# OpenTCU.net
KiCad netlist of a schematic drawn in EasyEDA
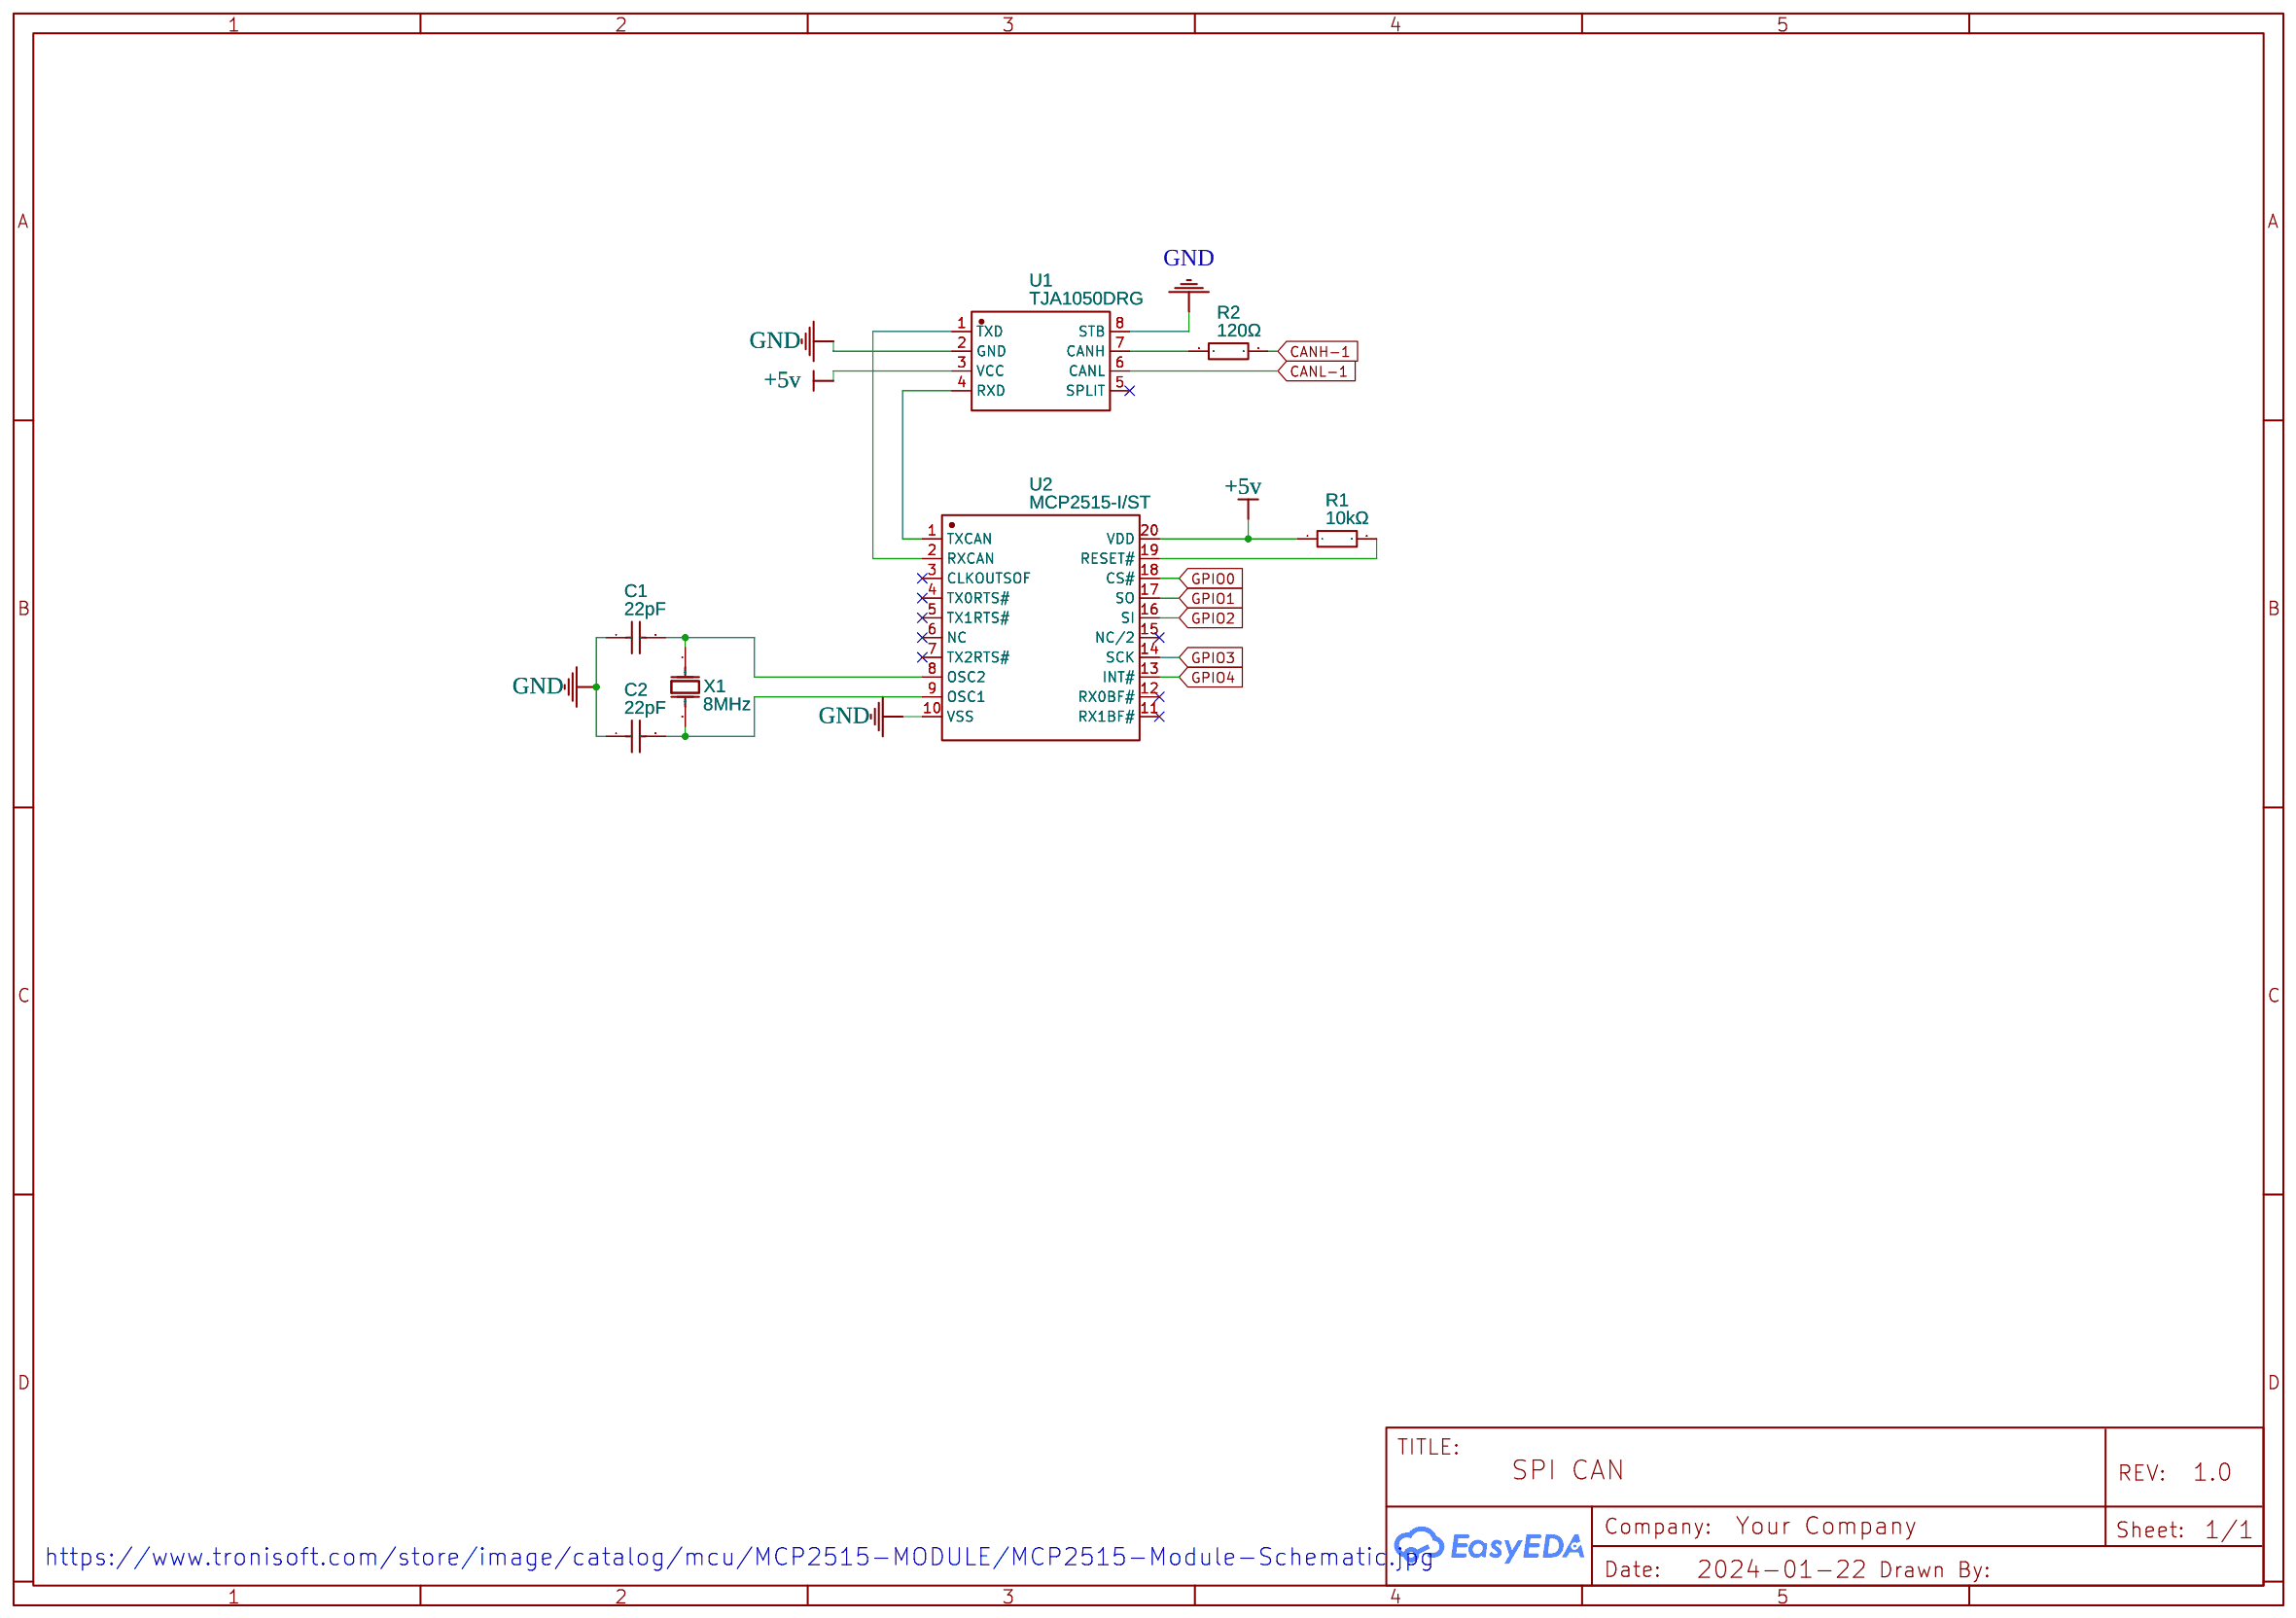
[diagram p0: SPI CAN]
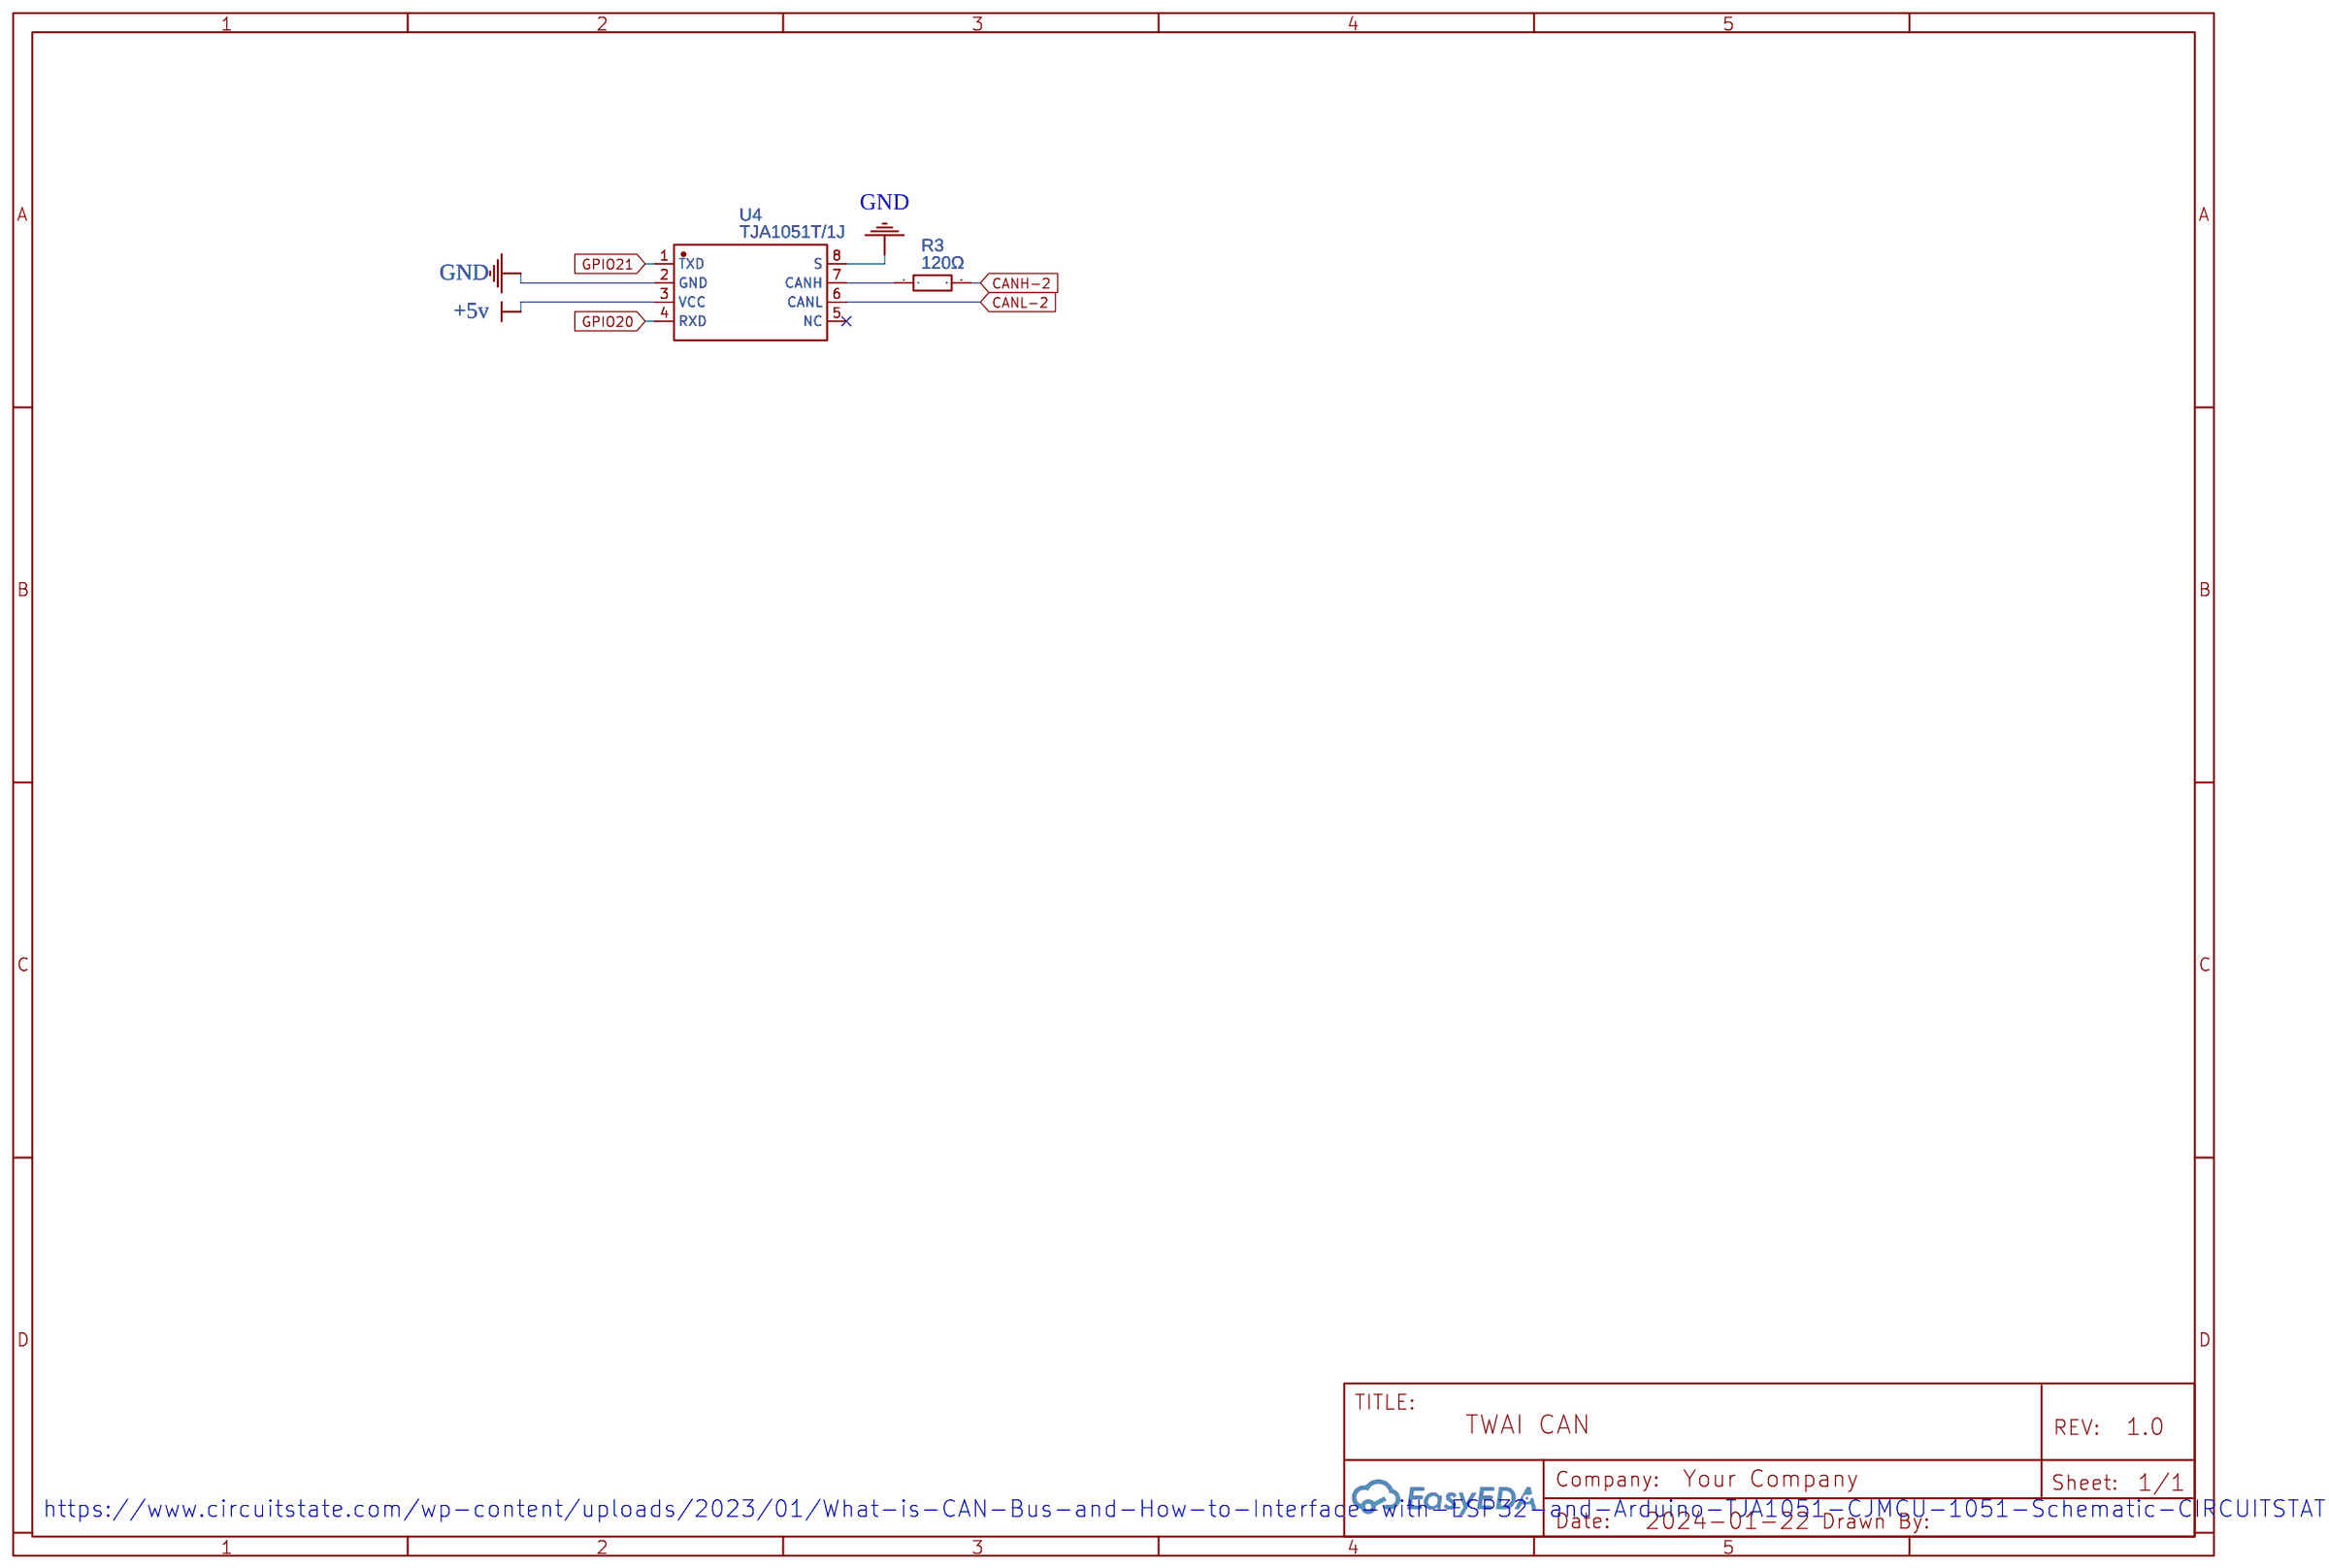
[diagram p1: TWAI CAN]
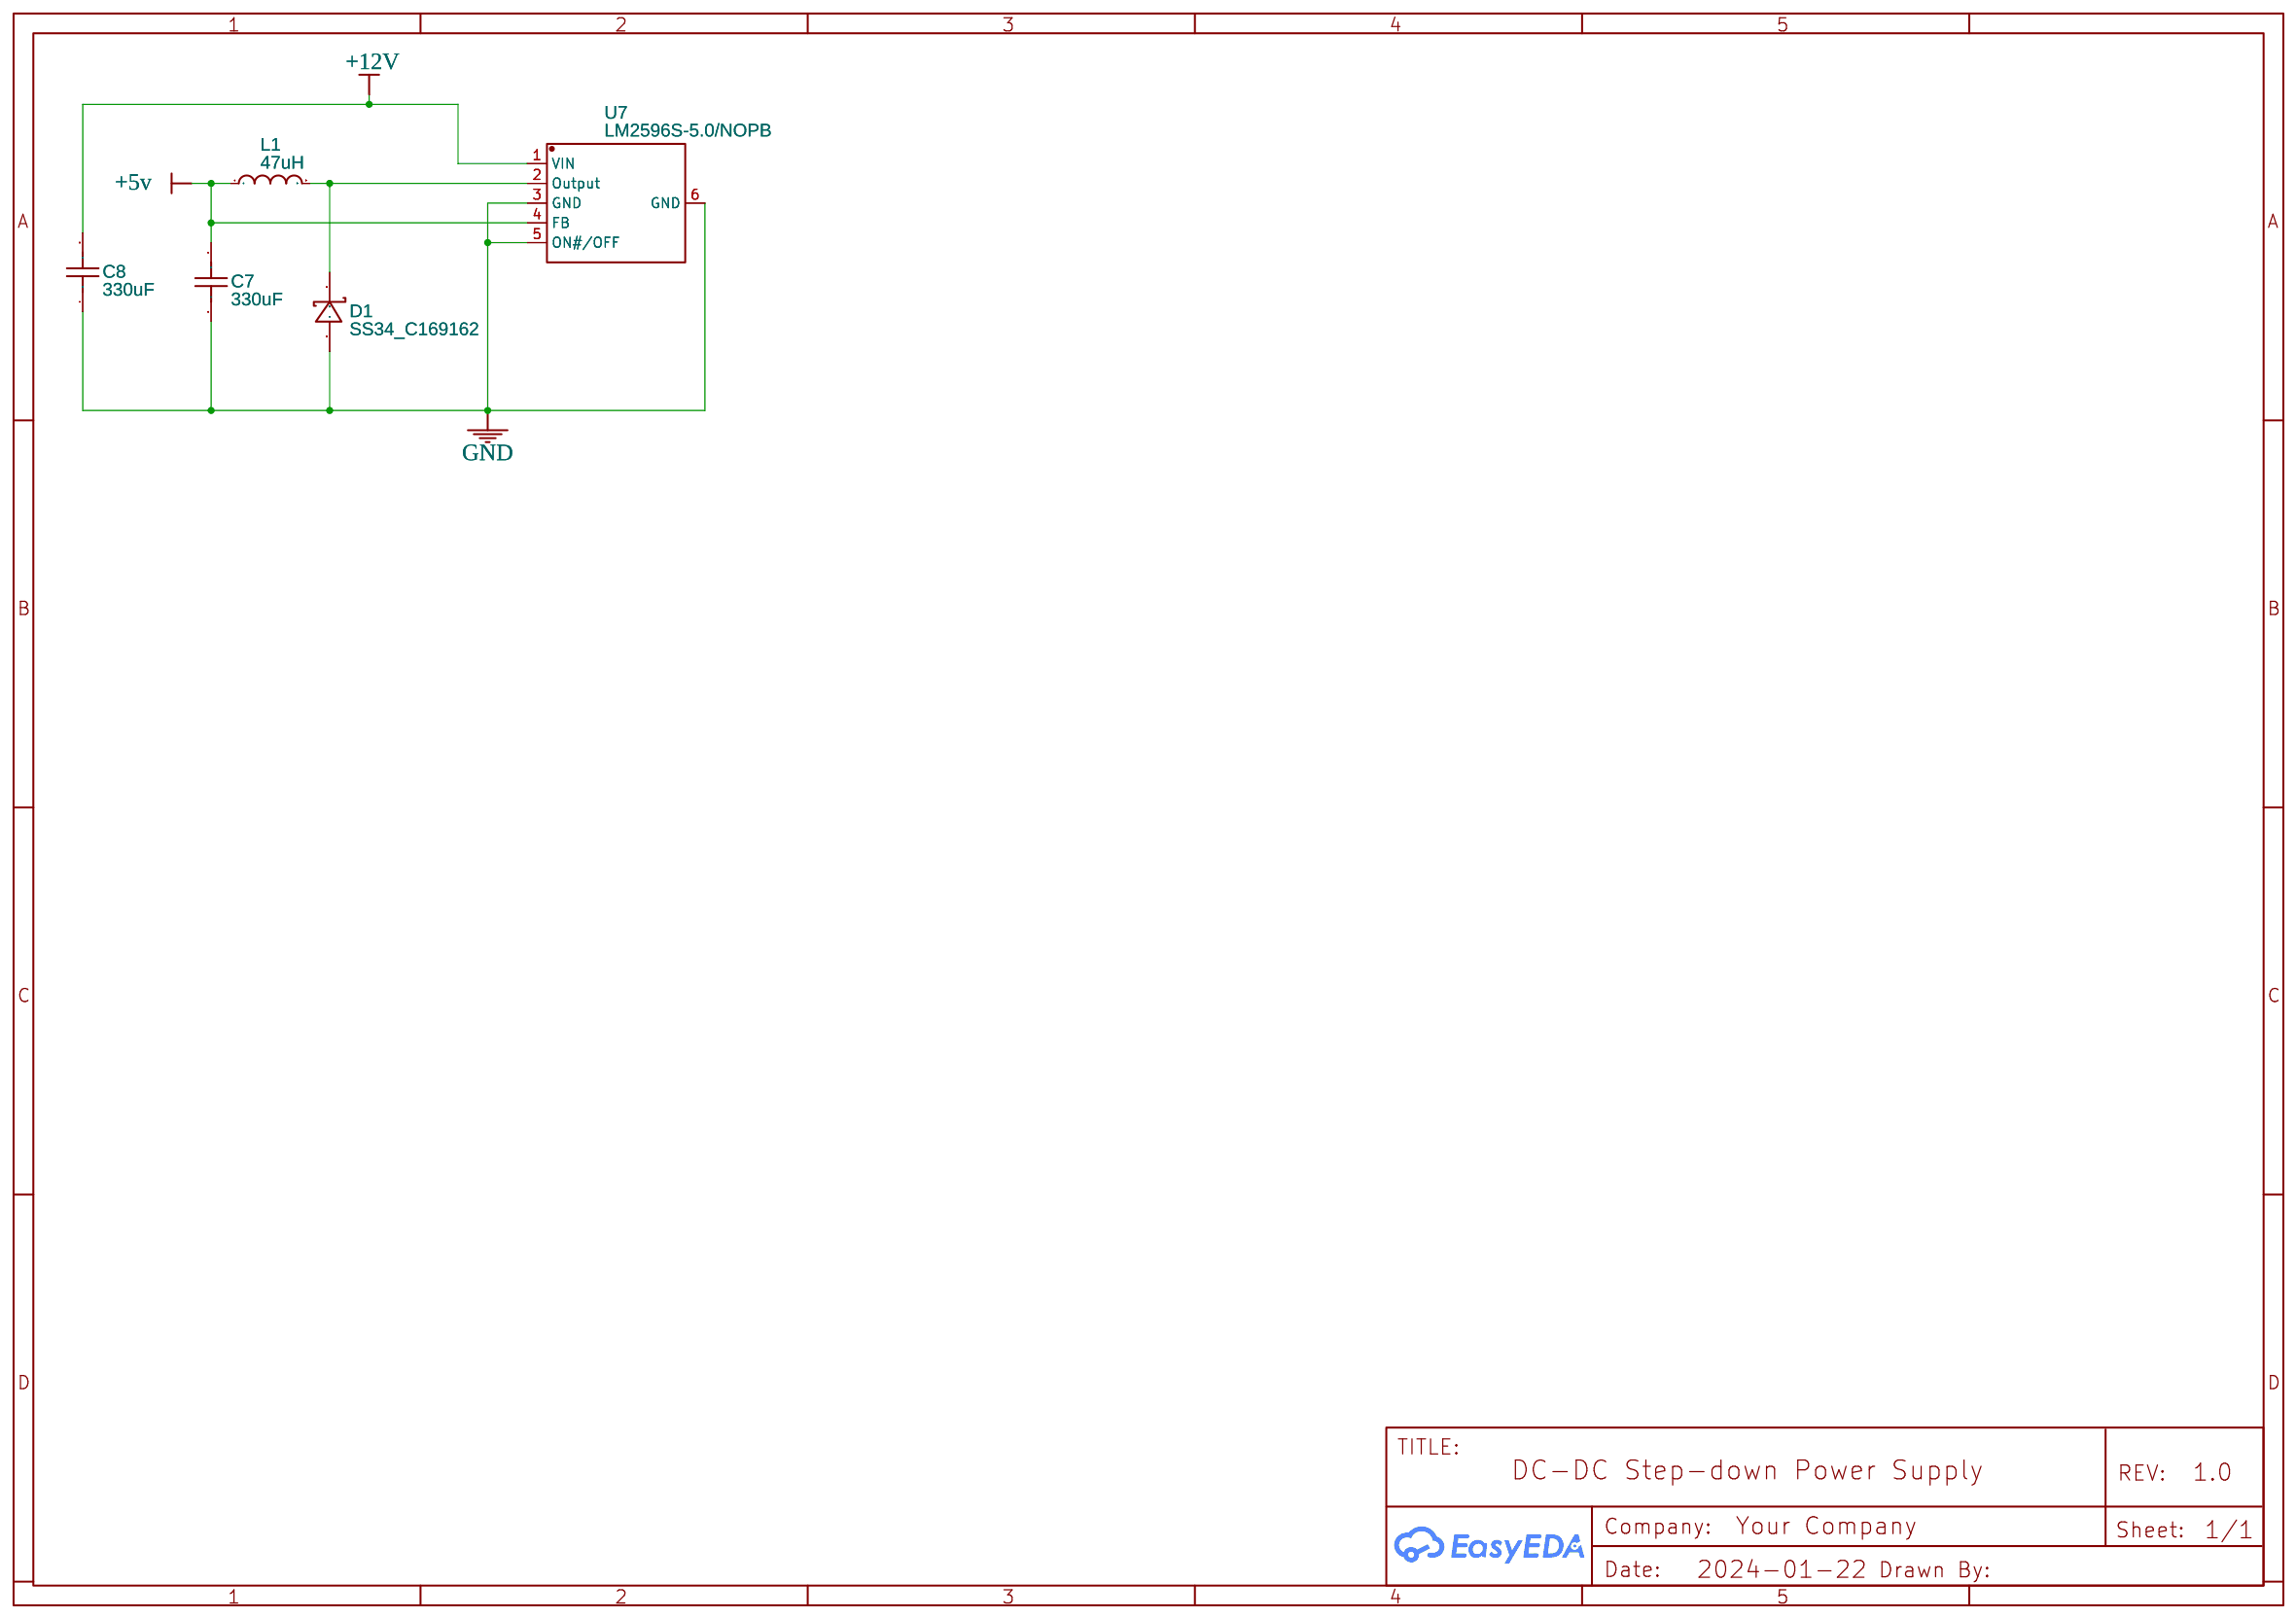
[diagram p2: DC-DC Step-down Power Supply]
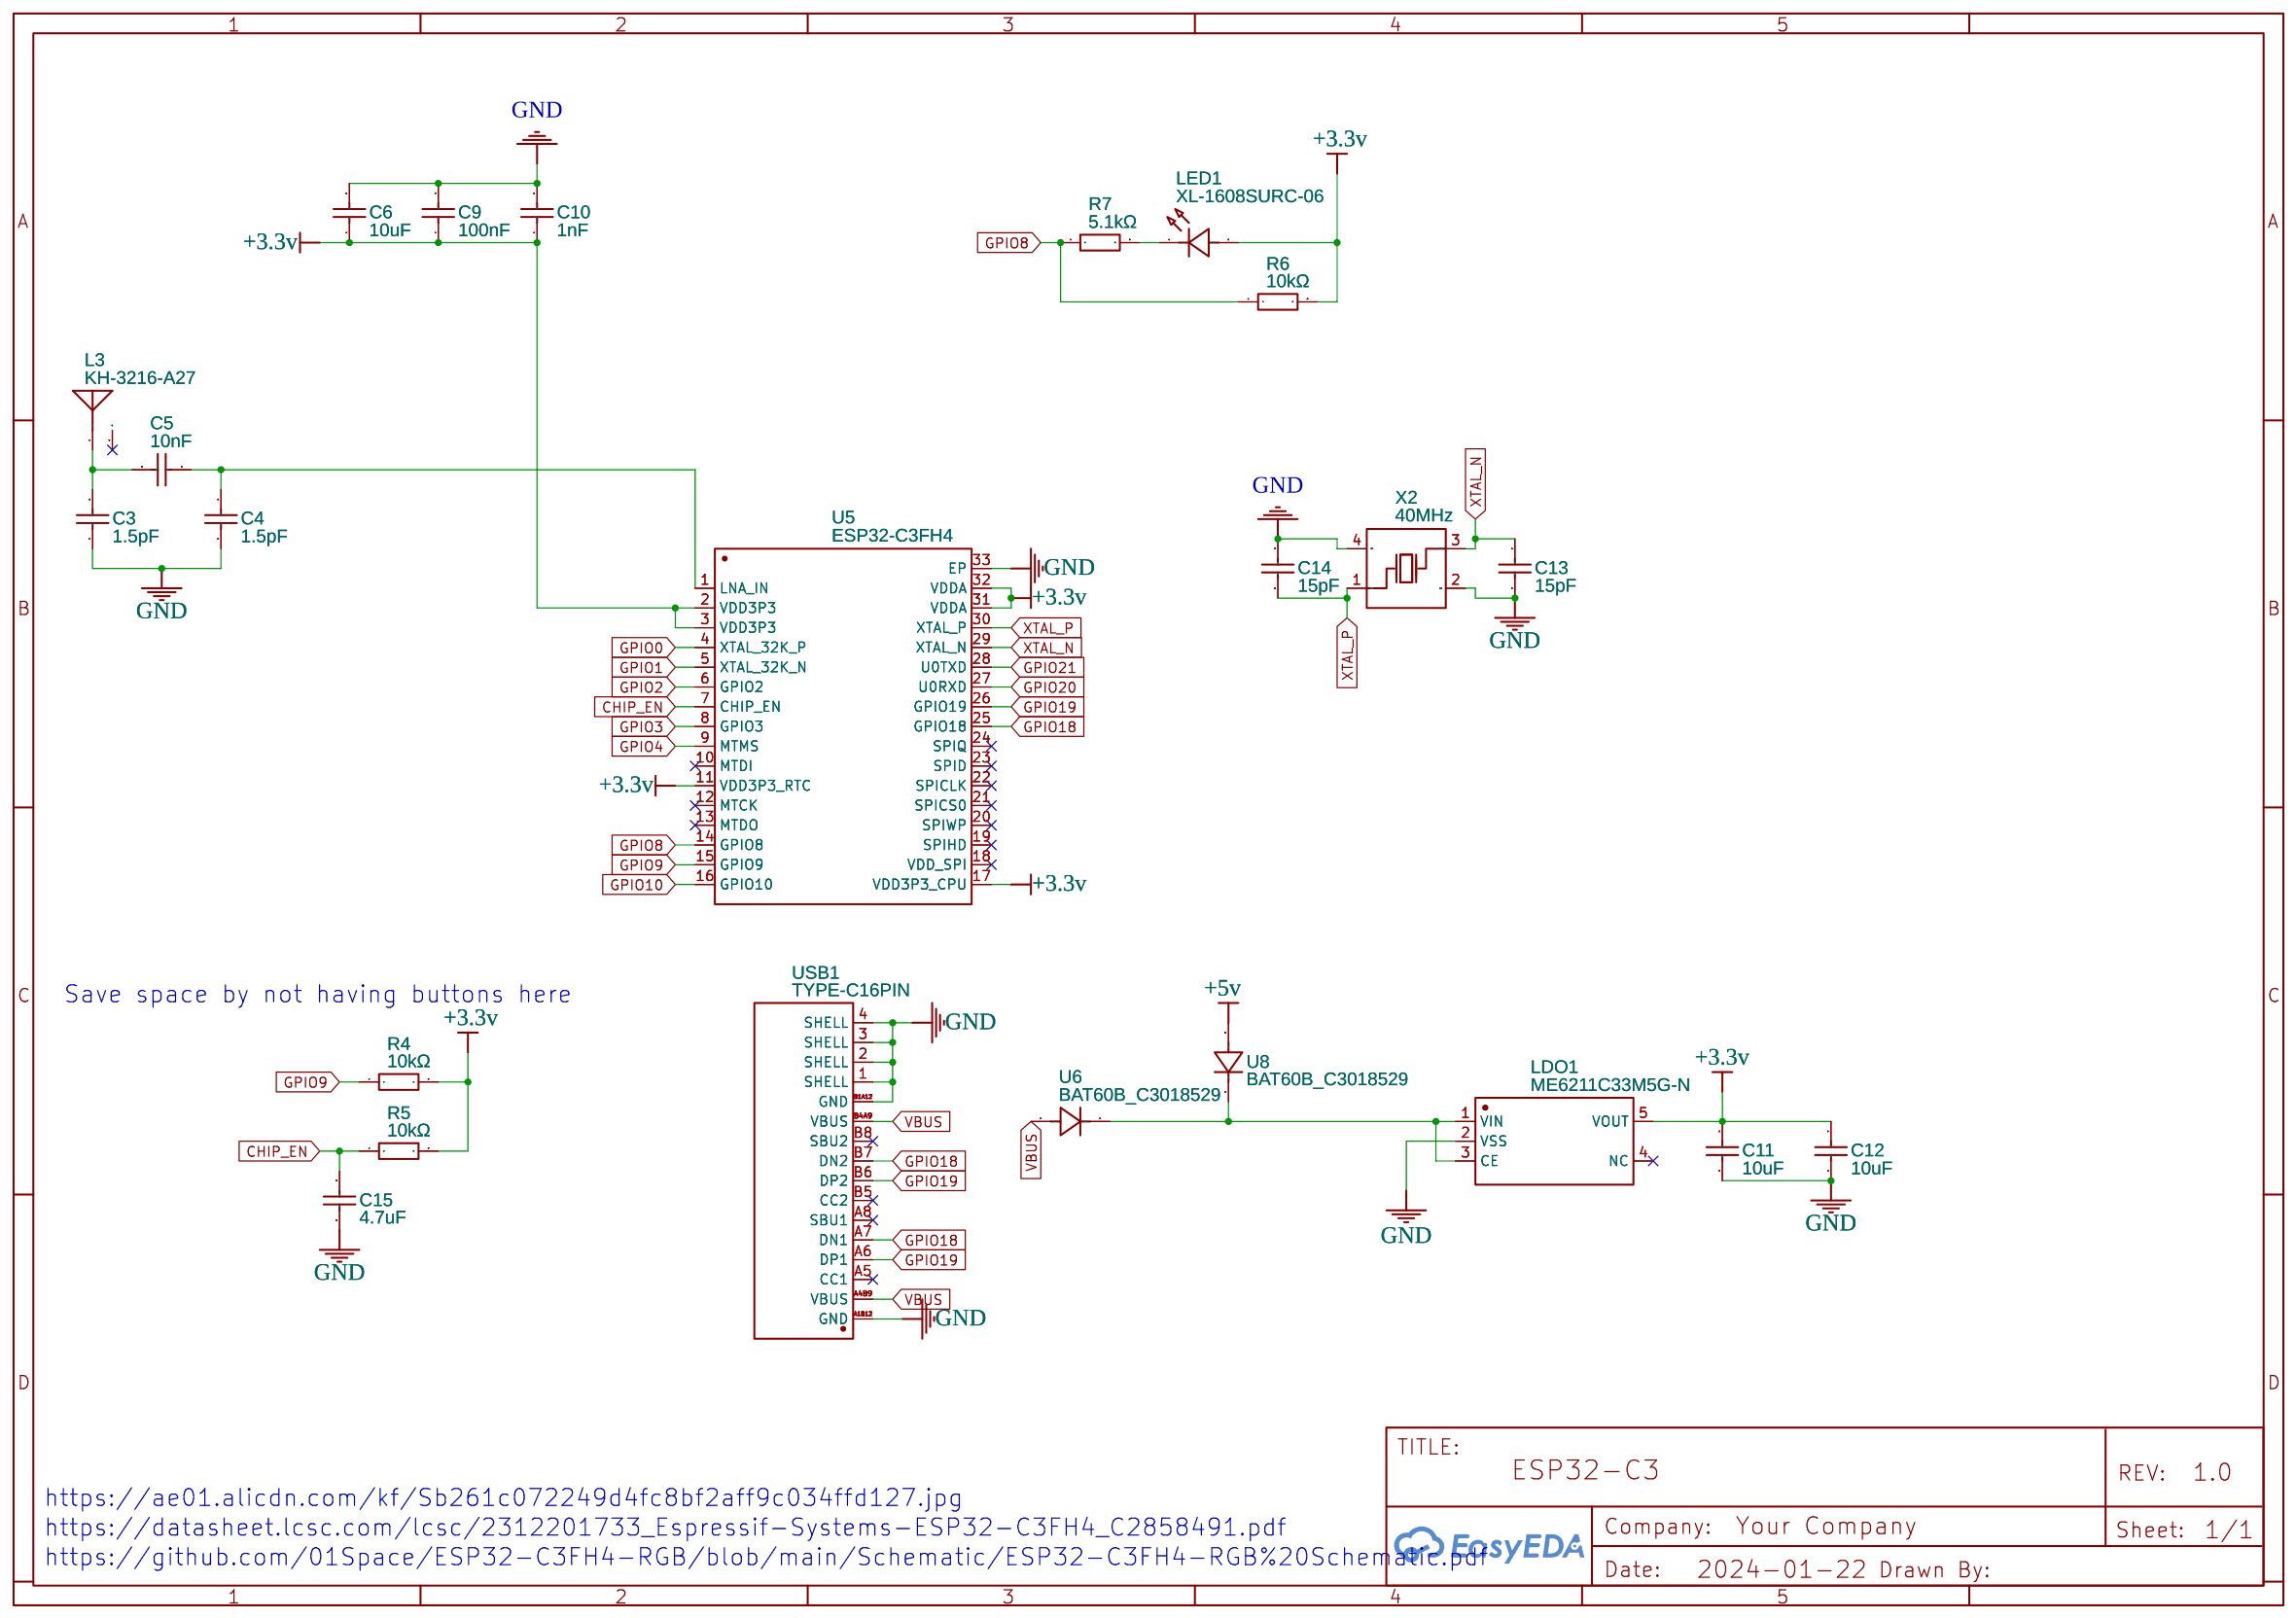
[diagram p3: ESP32-C3]
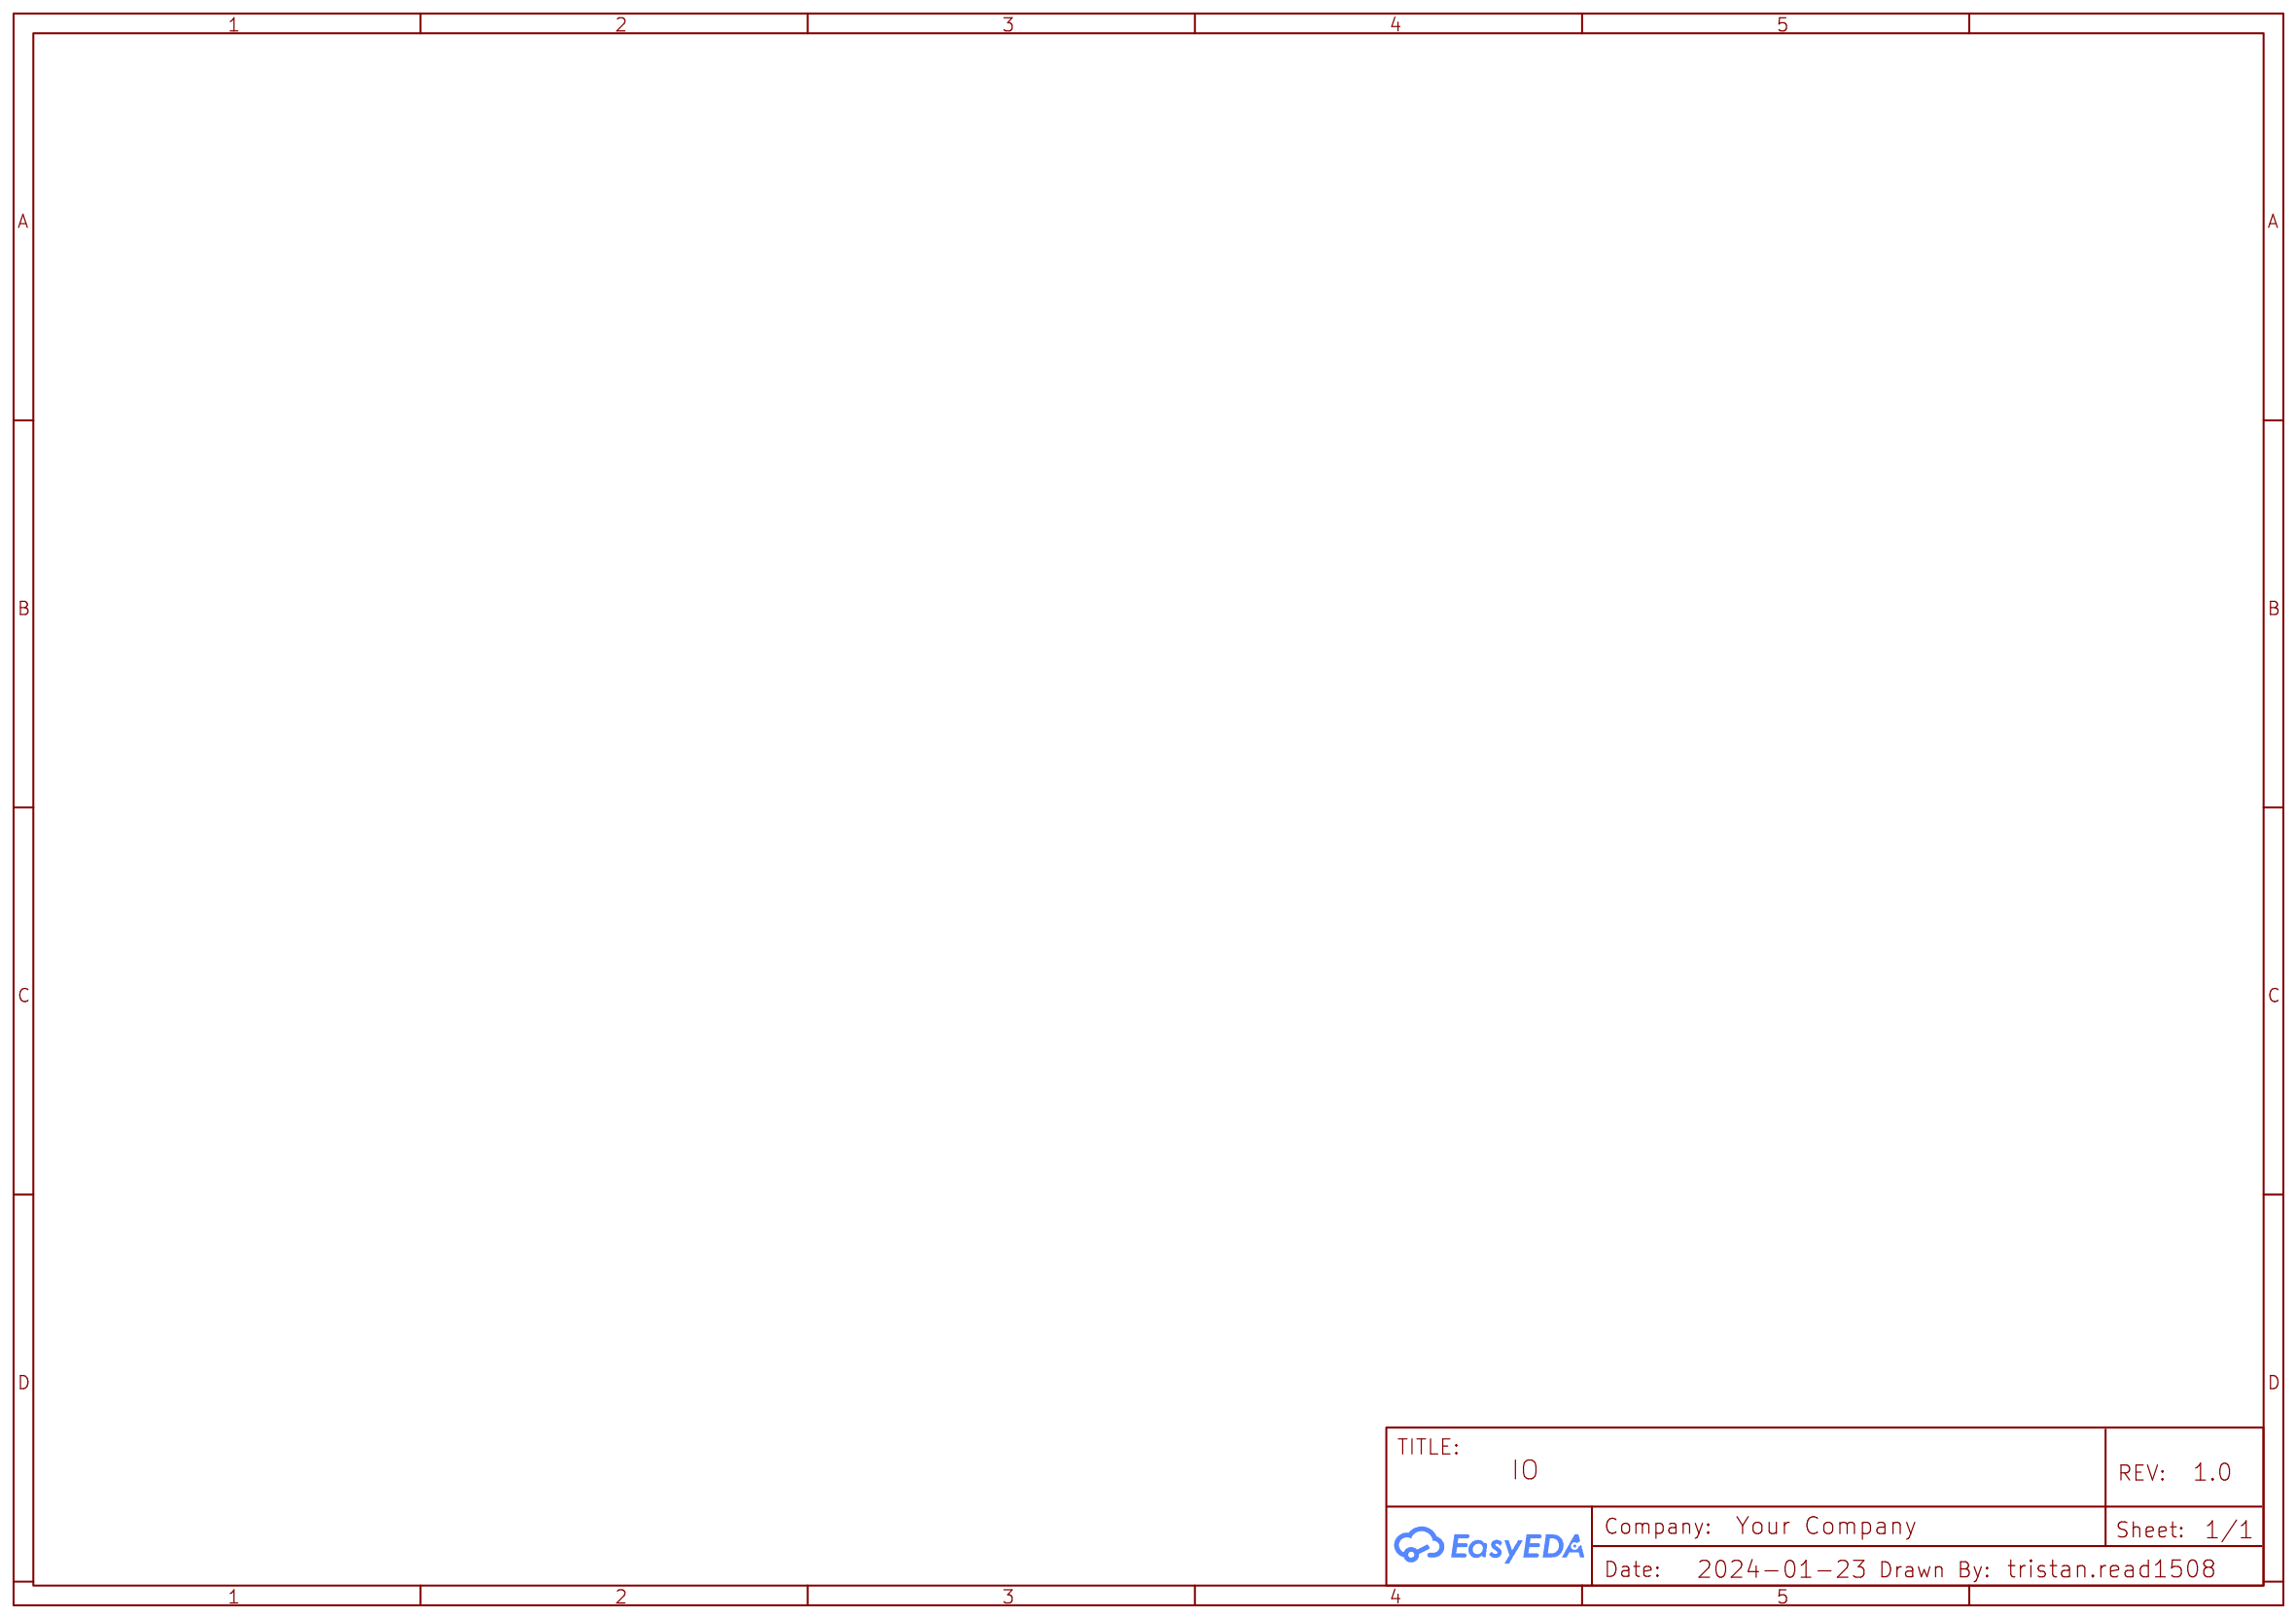
[diagram p4: IO]

(export (version "E")
  (design (tool "Eeschema 10.0.6"))
  (components
    (comp (ref "C1")
      (value "22pF")
      (fields (field (name "Manufacturer Part") "0402CG220J500NT") (field (name "Manufacturer") "FH(风华)"))
      (libsource (lib "") (part "0402CG220J500NT"))
    )
    (comp (ref "C2")
      (value "22pF")
      (fields (field (name "Manufacturer Part") "0402CG220J500NT") (field (name "Manufacturer") "FH(风华)"))
      (libsource (lib "") (part "0402CG220J500NT"))
    )
    (comp (ref "R1")
      (value "10kΩ")
      (fields (field (name "Manufacturer Part") "RC0603FR-0710KL") (field (name "Manufacturer") "YAGEO(国巨)"))
      (libsource (lib "") (part "RC0603FR-0710KL"))
    )
    (comp (ref "R2")
      (value "120Ω")
      (fields
        (field (name "Manufacturer Part") "0603WAF1200T5E")
        (field (name "Manufacturer") "UNI-ROYAL(厚声)")
      )
      (libsource (lib "") (part "0603WAF1200T5E"))
    )
    (comp (ref "U1")
      (value "TJA1050DRG")
      (fields (field (name "Manufacturer") "HGC(深圳汉芯)"))
      (libsource (lib "") (part "TJA1050DRG"))
    )
    (comp (ref "U2")
      (value "MCP2515-I/ST")
      (fields (field (name "Manufacturer") "MICROCHIP(美国微芯)"))
      (libsource (lib "") (part "MCP2515-I/ST"))
    )
    (comp (ref "X1")
      (value "8MHz")
      (fields (field (name "Manufacturer Part") "X50328MSB2GI") (field (name "Manufacturer") "YXC(扬兴晶振)"))
      (libsource (lib "") (part "X50328MSB2GI"))
    )
    (comp (ref "R3")
      (value "120Ω")
      (fields
        (field (name "Manufacturer Part") "0603WAF1200T5E")
        (field (name "Manufacturer") "UNI-ROYAL(厚声)")
      )
      (libsource (lib "") (part "0603WAF1200T5E"))
    )
    (comp (ref "U4")
      (value "TJA1051T/1J")
      (fields (field (name "Manufacturer") "NXP(恩智浦)"))
      (libsource (lib "") (part "TJA1051T/1J"))
    )
    (comp (ref "C7")
      (value "330uF")
      (fields
        (field (name "Manufacturer Part") "GRM32ER60G337ME05L")
        (field (name "Manufacturer") "muRata(村田)")
      )
      (libsource (lib "") (part "GRM32ER60G337ME05L_1"))
    )
    (comp (ref "C8")
      (value "330uF")
      (fields
        (field (name "Manufacturer Part") "GRM32ER60G337ME05L")
        (field (name "Manufacturer") "muRata(村田)")
      )
      (libsource (lib "") (part "GRM32ER60G337ME05L"))
    )
    (comp (ref "D1")
      (value "SS34_C169162")
      (fields (field (name "Manufacturer Part") "SS34"))
      (libsource (lib "") (part "SS34_C169162"))
    )
    (comp (ref "L1")
      (value "47uH")
      (fields (field (name "Manufacturer Part") "CYA0650-47UH") (field (name "Manufacturer") "SHOU HAN(首韩)"))
      (libsource (lib "") (part "CYA0650-47UH"))
    )
    (comp (ref "U7")
      (value "LM2596S-5.0/NOPB")
      (fields (field (name "Manufacturer") "TI(德州仪器)"))
      (libsource (lib "") (part "LM2596S-5.0/NOPB"))
    )
    (comp (ref "C3")
      (value "1.5pF")
      (fields (field (name "Manufacturer Part") "0402CG1R5C500NT") (field (name "Manufacturer") "FH(风华)"))
      (libsource (lib "") (part "0402CG1R5C500NT"))
    )
    (comp (ref "C4")
      (value "1.5pF")
      (fields (field (name "Manufacturer Part") "0402CG1R5C500NT") (field (name "Manufacturer") "FH(风华)"))
      (libsource (lib "") (part "0402CG1R5C500NT"))
    )
    (comp (ref "C5")
      (value "10nF")
      (fields
        (field (name "Manufacturer Part") "CC0402KRX7R9BB103")
        (field (name "Manufacturer") "YAGEO(国巨)")
      )
      (libsource (lib "") (part "CC0402KRX7R9BB103"))
    )
    (comp (ref "C6")
      (value "10uF")
      (fields
        (field (name "Manufacturer Part") "CL05A106MQ5NUNC")
        (field (name "Manufacturer") "SAMSUNG(三星)")
      )
      (libsource (lib "") (part "CL05A106MQ5NUNC"))
    )
    (comp (ref "C9")
      (value "100nF")
      (fields (field (name "Manufacturer Part") "0603B104K500NT") (field (name "Manufacturer") "FH(风华)"))
      (libsource (lib "") (part "0603B104K500NT"))
    )
    (comp (ref "C10")
      (value "1nF")
      (fields
        (field (name "Manufacturer Part") "CC0402KRX7R9BB102")
        (field (name "Manufacturer") "YAGEO(国巨)")
      )
      (libsource (lib "") (part "CC0402KRX7R9BB102"))
    )
    (comp (ref "C11")
      (value "10uF")
      (fields
        (field (name "Manufacturer Part") "CL05A106MQ5NUNC")
        (field (name "Manufacturer") "SAMSUNG(三星)")
      )
      (libsource (lib "") (part "CL05A106MQ5NUNC"))
    )
    (comp (ref "C12")
      (value "10uF")
      (fields
        (field (name "Manufacturer Part") "CL05A106MQ5NUNC")
        (field (name "Manufacturer") "SAMSUNG(三星)")
      )
      (libsource (lib "") (part "CL05A106MQ5NUNC"))
    )
    (comp (ref "C13")
      (value "15pF")
      (fields (field (name "Manufacturer Part") "0402CG150J500NT") (field (name "Manufacturer") "FH(风华)"))
      (libsource (lib "") (part "0402CG150J500NT"))
    )
    (comp (ref "C14")
      (value "15pF")
      (fields (field (name "Manufacturer Part") "0402CG150J500NT") (field (name "Manufacturer") "FH(风华)"))
      (libsource (lib "") (part "0402CG150J500NT"))
    )
    (comp (ref "C15")
      (value "4.7uF")
      (fields
        (field (name "Manufacturer Part") "CL10A475KP8NNNC")
        (field (name "Manufacturer") "SAMSUNG(三星)")
      )
      (libsource (lib "") (part "CL10A475KP8NNNC"))
    )
    (comp (ref "L3")
      (value "KH-3216-A27")
      (fields (field (name "Manufacturer") "kinghelm(金航标)"))
      (libsource (lib "") (part "KH-3216-A27"))
    )
    (comp (ref "LDO1")
      (value "ME6211C33M5G-N")
      (fields (field (name "Manufacturer") "MICRONE(南京微盟)"))
      (libsource (lib "") (part "ME6211C33M5G-N"))
    )
    (comp (ref "LED1")
      (value "XL-1608SURC-06")
      (fields (field (name "Manufacturer") "XINGLIGHT(成兴光)"))
      (libsource (lib "") (part "XL-1608SURC-06"))
    )
    (comp (ref "R4")
      (value "10kΩ")
      (fields (field (name "Manufacturer Part") "RC0603FR-0710KL") (field (name "Manufacturer") "YAGEO(国巨)"))
      (libsource (lib "") (part "RC0603FR-0710KL"))
    )
    (comp (ref "R5")
      (value "10kΩ")
      (fields (field (name "Manufacturer Part") "RC0603FR-0710KL") (field (name "Manufacturer") "YAGEO(国巨)"))
      (libsource (lib "") (part "RC0603FR-0710KL"))
    )
    (comp (ref "R6")
      (value "10kΩ")
      (fields (field (name "Manufacturer Part") "RC0603FR-0710KL") (field (name "Manufacturer") "YAGEO(国巨)"))
      (libsource (lib "") (part "RC0603FR-0710KL"))
    )
    (comp (ref "R7")
      (value "5.1kΩ")
      (fields
        (field (name "Manufacturer Part") "0603WAF5101T5E")
        (field (name "Manufacturer") "UNI-ROYAL(厚声)")
      )
      (libsource (lib "") (part "0603WAF5101T5E"))
    )
    (comp (ref "U5")
      (value "ESP32-C3FH4")
      (fields (field (name "Manufacturer") "ESPRESSIF(乐鑫)"))
      (libsource (lib "") (part "ESP32-C3FH4"))
    )
    (comp (ref "U6")
      (value "BAT60B_C3018529")
      (fields (field (name "Manufacturer Part") "BAT60B") (field (name "Manufacturer") "FUXINSEMI(富芯森美)"))
      (libsource (lib "") (part "BAT60B_C3018529_1"))
    )
    (comp (ref "U8")
      (value "BAT60B_C3018529")
      (fields (field (name "Manufacturer Part") "BAT60B") (field (name "Manufacturer") "FUXINSEMI(富芯森美)"))
      (libsource (lib "") (part "BAT60B_C3018529"))
    )
    (comp (ref "USB1")
      (value "TYPE-C16PIN")
      (fields (field (name "Manufacturer") "SHOU HAN(首韩)"))
      (libsource (lib "") (part "TYPE-C16PIN"))
    )
    (comp (ref "X2")
      (value "40MHz")
      (fields (field (name "Manufacturer Part") "X322540MPB4SI") (field (name "Manufacturer") "YXC(扬兴晶振)"))
      (libsource (lib "") (part "X322540MPB4SI"))
    )
  )
  (nets
    (net (code "1") (name "+3.3v") (class "Default")
      (node (ref "C10") (pin "1") (pinfunction "1_1") (pintype "input"))
      (node (ref "C11") (pin "2") (pinfunction "2_2") (pintype "input"))
      (node (ref "C12") (pin "2") (pinfunction "2_2") (pintype "input"))
      (node (ref "C6") (pin "1") (pinfunction "1_1") (pintype "input"))
      (node (ref "C9") (pin "1") (pinfunction "1_1") (pintype "input"))
      (node (ref "LDO1") (pin "5") (pinfunction "VOUT_5") (pintype "unspecified"))
      (node (ref "LED1") (pin "2") (pinfunction "A_2") (pintype "unspecified"))
      (node (ref "R4") (pin "2") (pinfunction "2_2") (pintype "input"))
      (node (ref "R5") (pin "2") (pinfunction "2_2") (pintype "input"))
      (node (ref "R6") (pin "2") (pinfunction "2_2") (pintype "input"))
      (node (ref "U5") (pin "11") (pinfunction "VDD3P3_RTC_11") (pintype "unspecified"))
      (node (ref "U5") (pin "17") (pinfunction "VDD3P3_CPU_17") (pintype "unspecified"))
      (node (ref "U5") (pin "2") (pinfunction "VDD3P3_2") (pintype "unspecified"))
      (node (ref "U5") (pin "3") (pinfunction "VDD3P3_3") (pintype "unspecified"))
      (node (ref "U5") (pin "31") (pinfunction "VDDA_31") (pintype "unspecified"))
      (node (ref "U5") (pin "32") (pinfunction "VDDA_32") (pintype "unspecified"))
    )
    (net (code "2") (name "+5v") (class "Default")
      (node (ref "C7") (pin "1") (pinfunction "1_1") (pintype "unspecified"))
      (node (ref "L1") (pin "1") (pinfunction "1_1") (pintype "unspecified"))
      (node (ref "R1") (pin "1") (pinfunction "1_1") (pintype "input"))
      (node (ref "U1") (pin "3") (pinfunction "VCC_3") (pintype "unspecified"))
      (node (ref "U2") (pin "20") (pinfunction "VDD_20") (pintype "unspecified"))
      (node (ref "U4") (pin "3") (pinfunction "VCC_3") (pintype "unspecified"))
      (node (ref "U7") (pin "4") (pinfunction "FB_4") (pintype "unspecified"))
      (node (ref "U8") (pin "2") (pinfunction "A_2") (pintype "unspecified"))
    )
    (net (code "3") (name "+12V") (class "Default")
      (node (ref "C8") (pin "2") (pinfunction "2_2") (pintype "unspecified"))
      (node (ref "U7") (pin "1") (pinfunction "VIN_1") (pintype "unspecified"))
    )
    (net (code "4") (name "CANH-1") (class "Default")
      (node (ref "R2") (pin "2") (pinfunction "2_2") (pintype "input"))
    )
    (net (code "5") (name "CANH-2") (class "Default")
      (node (ref "R3") (pin "2") (pinfunction "2_2") (pintype "input"))
    )
    (net (code "6") (name "CANL-1") (class "Default")
      (node (ref "U1") (pin "6") (pinfunction "CANL_6") (pintype "unspecified"))
    )
    (net (code "7") (name "CANL-2") (class "Default")
      (node (ref "U4") (pin "6") (pinfunction "CANL_6") (pintype "unspecified"))
    )
    (net (code "8") (name "CHIP_EN") (class "Default")
      (node (ref "C15") (pin "2") (pinfunction "2_2") (pintype "input"))
      (node (ref "R5") (pin "1") (pinfunction "1_1") (pintype "input"))
      (node (ref "U5") (pin "7") (pinfunction "CHIP_EN_7") (pintype "unspecified"))
    )
    (net (code "9") (name "GND") (class "Default")
      (node (ref "C1") (pin "1") (pinfunction "1_1") (pintype "input"))
      (node (ref "C10") (pin "2") (pinfunction "2_2") (pintype "input"))
      (node (ref "C11") (pin "1") (pinfunction "1_1") (pintype "input"))
      (node (ref "C12") (pin "1") (pinfunction "1_1") (pintype "input"))
      (node (ref "C13") (pin "1") (pinfunction "1_1") (pintype "input"))
      (node (ref "C14") (pin "2") (pinfunction "2_2") (pintype "input"))
      (node (ref "C15") (pin "1") (pinfunction "1_1") (pintype "input"))
      (node (ref "C2") (pin "1") (pinfunction "1_1") (pintype "input"))
      (node (ref "C3") (pin "1") (pinfunction "1_1") (pintype "input"))
      (node (ref "C4") (pin "1") (pinfunction "1_1") (pintype "input"))
      (node (ref "C6") (pin "2") (pinfunction "2_2") (pintype "input"))
      (node (ref "C7") (pin "2") (pinfunction "2_2") (pintype "unspecified"))
      (node (ref "C8") (pin "1") (pinfunction "1_1") (pintype "unspecified"))
      (node (ref "C9") (pin "2") (pinfunction "2_2") (pintype "input"))
      (node (ref "D1") (pin "2") (pinfunction "A_2") (pintype "unspecified"))
      (node (ref "LDO1") (pin "2") (pinfunction "VSS_2") (pintype "unspecified"))
      (node (ref "U1") (pin "2") (pinfunction "GND_2") (pintype "unspecified"))
      (node (ref "U1") (pin "8") (pinfunction "STB_8") (pintype "unspecified"))
      (node (ref "U2") (pin "10") (pinfunction "VSS_10") (pintype "unspecified"))
      (node (ref "U4") (pin "2") (pinfunction "GND_2") (pintype "unspecified"))
      (node (ref "U4") (pin "8") (pinfunction "S_8") (pintype "unspecified"))
      (node (ref "U5") (pin "33") (pinfunction "EP_33") (pintype "unspecified"))
      (node (ref "U7") (pin "3") (pinfunction "GND_3") (pintype "unspecified"))
      (node (ref "U7") (pin "5") (pinfunction "ON#/OFF_5") (pintype "unspecified"))
      (node (ref "U7") (pin "6") (pinfunction "GND_6") (pintype "unspecified"))
      (node (ref "USB1") (pin "1") (pinfunction "SHELL_1") (pintype "unspecified"))
      (node (ref "USB1") (pin "2") (pinfunction "SHELL_2") (pintype "unspecified"))
      (node (ref "USB1") (pin "3") (pinfunction "SHELL_3") (pintype "unspecified"))
      (node (ref "USB1") (pin "4") (pinfunction "SHELL_4") (pintype "unspecified"))
      (node (ref "USB1") (pin "A1B12") (pinfunction "GND_A1B12") (pintype "unspecified"))
      (node (ref "USB1") (pin "B1A12") (pinfunction "GND_B1A12") (pintype "unspecified"))
      (node (ref "X2") (pin "2") (pinfunction "GND_2") (pintype "unspecified"))
      (node (ref "X2") (pin "4") (pinfunction "GND_4") (pintype "unspecified"))
    )
    (net (code "10") (name "GPIO0") (class "Default")
      (node (ref "U2") (pin "18") (pinfunction "CS#_18") (pintype "unspecified"))
      (node (ref "U5") (pin "4") (pinfunction "XTAL_32K_P_4") (pintype "unspecified"))
    )
    (net (code "11") (name "GPIO1") (class "Default")
      (node (ref "U2") (pin "17") (pinfunction "SO_17") (pintype "unspecified"))
      (node (ref "U5") (pin "5") (pinfunction "XTAL_32K_N_5") (pintype "unspecified"))
    )
    (net (code "12") (name "GPIO2") (class "Default")
      (node (ref "U2") (pin "16") (pinfunction "SI_16") (pintype "unspecified"))
      (node (ref "U5") (pin "6") (pinfunction "GPIO2_6") (pintype "unspecified"))
    )
    (net (code "13") (name "GPIO3") (class "Default")
      (node (ref "U2") (pin "14") (pinfunction "SCK_14") (pintype "unspecified"))
      (node (ref "U5") (pin "8") (pinfunction "GPIO3_8") (pintype "unspecified"))
    )
    (net (code "14") (name "GPIO4") (class "Default")
      (node (ref "U2") (pin "13") (pinfunction "INT#_13") (pintype "unspecified"))
      (node (ref "U5") (pin "9") (pinfunction "MTMS_9") (pintype "unspecified"))
    )
    (net (code "15") (name "GPIO8") (class "Default")
      (node (ref "R6") (pin "1") (pinfunction "1_1") (pintype "input"))
      (node (ref "R7") (pin "1") (pinfunction "1_1") (pintype "input"))
      (node (ref "U5") (pin "14") (pinfunction "GPIO8_14") (pintype "unspecified"))
    )
    (net (code "16") (name "GPIO9") (class "Default")
      (node (ref "R4") (pin "1") (pinfunction "1_1") (pintype "input"))
      (node (ref "U5") (pin "15") (pinfunction "GPIO9_15") (pintype "unspecified"))
    )
    (net (code "17") (name "GPIO10") (class "Default")
      (node (ref "U5") (pin "16") (pinfunction "GPIO10_16") (pintype "unspecified"))
    )
    (net (code "18") (name "GPIO18") (class "Default")
      (node (ref "U5") (pin "25") (pinfunction "GPIO18_25") (pintype "unspecified"))
      (node (ref "USB1") (pin "A7") (pinfunction "DN1_A7") (pintype "unspecified"))
      (node (ref "USB1") (pin "B7") (pinfunction "DN2_B7") (pintype "unspecified"))
    )
    (net (code "19") (name "GPIO19") (class "Default")
      (node (ref "U5") (pin "26") (pinfunction "GPIO19_26") (pintype "unspecified"))
      (node (ref "USB1") (pin "A6") (pinfunction "DP1_A6") (pintype "unspecified"))
      (node (ref "USB1") (pin "B6") (pinfunction "DP2_B6") (pintype "unspecified"))
    )
    (net (code "20") (name "GPIO20") (class "Default")
      (node (ref "U4") (pin "4") (pinfunction "RXD_4") (pintype "unspecified"))
      (node (ref "U5") (pin "27") (pinfunction "U0RXD_27") (pintype "unspecified"))
    )
    (net (code "21") (name "GPIO21") (class "Default")
      (node (ref "U4") (pin "1") (pinfunction "TXD_1") (pintype "unspecified"))
      (node (ref "U5") (pin "28") (pinfunction "U0TXD_28") (pintype "unspecified"))
    )
    (net (code "22") (name "Net-(D1-C)") (class "Default")
      (node (ref "D1") (pin "1") (pinfunction "C_1") (pintype "unspecified"))
      (node (ref "L1") (pin "2") (pinfunction "2_2") (pintype "unspecified"))
      (node (ref "U7") (pin "2") (pinfunction "Output_2") (pintype "unspecified"))
    )
    (net (code "23") (name "Net-(L3-ANT)") (class "Default")
      (node (ref "C3") (pin "2") (pinfunction "2_2") (pintype "input"))
      (node (ref "C5") (pin "1") (pinfunction "1_1") (pintype "input"))
      (node (ref "L3") (pin "1") (pinfunction "ANT_1") (pintype "unspecified"))
    )
    (net (code "24") (name "Net-(LDO1-CE)") (class "Default")
      (node (ref "LDO1") (pin "1") (pinfunction "VIN_1") (pintype "unspecified"))
      (node (ref "LDO1") (pin "3") (pinfunction "CE_3") (pintype "unspecified"))
      (node (ref "U6") (pin "1") (pinfunction "K_1") (pintype "unspecified"))
      (node (ref "U8") (pin "1") (pinfunction "K_1") (pintype "unspecified"))
    )
    (net (code "25") (name "Net-(LED1-K)") (class "Default")
      (node (ref "LED1") (pin "1") (pinfunction "K_1") (pintype "unspecified"))
      (node (ref "R7") (pin "2") (pinfunction "2_2") (pintype "input"))
    )
    (net (code "26") (name "Net-(U1-CANH)") (class "Default")
      (node (ref "R2") (pin "1") (pinfunction "1_1") (pintype "input"))
      (node (ref "U1") (pin "7") (pinfunction "CANH_7") (pintype "unspecified"))
    )
    (net (code "27") (name "Net-(U1-RXD)") (class "Default")
      (node (ref "U1") (pin "4") (pinfunction "RXD_4") (pintype "unspecified"))
      (node (ref "U2") (pin "1") (pinfunction "TXCAN_1") (pintype "unspecified"))
    )
    (net (code "28") (name "Net-(U1-TXD)") (class "Default")
      (node (ref "U1") (pin "1") (pinfunction "TXD_1") (pintype "unspecified"))
      (node (ref "U2") (pin "2") (pinfunction "RXCAN_2") (pintype "unspecified"))
    )
    (net (code "29") (name "Net-(U2-OSC1)") (class "Default")
      (node (ref "C2") (pin "2") (pinfunction "2_2") (pintype "input"))
      (node (ref "U2") (pin "9") (pinfunction "OSC1_9") (pintype "unspecified"))
      (node (ref "X1") (pin "2") (pinfunction "OSC2_2") (pintype "input"))
    )
    (net (code "30") (name "Net-(U2-OSC2)") (class "Default")
      (node (ref "C1") (pin "2") (pinfunction "2_2") (pintype "input"))
      (node (ref "U2") (pin "8") (pinfunction "OSC2_8") (pintype "unspecified"))
      (node (ref "X1") (pin "1") (pinfunction "OSC1_1") (pintype "input"))
    )
    (net (code "31") (name "Net-(U2-RESET#)") (class "Default")
      (node (ref "R1") (pin "2") (pinfunction "2_2") (pintype "input"))
      (node (ref "U2") (pin "19") (pinfunction "RESET#_19") (pintype "unspecified"))
    )
    (net (code "32") (name "Net-(U4-CANH)") (class "Default")
      (node (ref "R3") (pin "1") (pinfunction "1_1") (pintype "input"))
      (node (ref "U4") (pin "7") (pinfunction "CANH_7") (pintype "unspecified"))
    )
    (net (code "33") (name "Net-(U5-LNA_IN)") (class "Default")
      (node (ref "C4") (pin "2") (pinfunction "2_2") (pintype "input"))
      (node (ref "C5") (pin "2") (pinfunction "2_2") (pintype "input"))
      (node (ref "U5") (pin "1") (pinfunction "LNA_IN_1") (pintype "unspecified"))
    )
    (net (code "34") (name "VBUS") (class "Default")
      (node (ref "U6") (pin "2") (pinfunction "A_2") (pintype "unspecified"))
      (node (ref "USB1") (pin "A4B9") (pinfunction "VBUS_A4B9") (pintype "unspecified"))
      (node (ref "USB1") (pin "B4A9") (pinfunction "VBUS_B4A9") (pintype "unspecified"))
    )
    (net (code "35") (name "XTAL_N") (class "Default")
      (node (ref "C13") (pin "2") (pinfunction "2_2") (pintype "input"))
      (node (ref "U5") (pin "29") (pinfunction "XTAL_N_29") (pintype "unspecified"))
      (node (ref "X2") (pin "3") (pinfunction "OSC2_3") (pintype "unspecified"))
    )
    (net (code "36") (name "XTAL_P") (class "Default")
      (node (ref "C14") (pin "1") (pinfunction "1_1") (pintype "input"))
      (node (ref "U5") (pin "30") (pinfunction "XTAL_P_30") (pintype "unspecified"))
      (node (ref "X2") (pin "1") (pinfunction "OSC1_1") (pintype "unspecified"))
    )
    (net (code "37") (name "unconnected-(L3-Pad2)") (class "Default")
      (node (ref "L3") (pin "2") (pinfunction "2_2") (pintype "unspecified+no_connect"))
    )
    (net (code "38") (name "unconnected-(LDO1-NC-Pad4)") (class "Default")
      (node (ref "LDO1") (pin "4") (pinfunction "NC_4") (pintype "unspecified+no_connect"))
    )
    (net (code "39") (name "unconnected-(U1-SPLIT-Pad5)") (class "Default")
      (node (ref "U1") (pin "5") (pinfunction "SPLIT_5") (pintype "unspecified+no_connect"))
    )
    (net (code "40") (name "unconnected-(U2-CLKOUTSOF-Pad3)") (class "Default")
      (node (ref "U2") (pin "3") (pinfunction "CLKOUTSOF_3") (pintype "unspecified+no_connect"))
    )
    (net (code "41") (name "unconnected-(U2-NC-Pad6)") (class "Default")
      (node (ref "U2") (pin "6") (pinfunction "NC_6") (pintype "unspecified+no_connect"))
    )
    (net (code "42") (name "unconnected-(U2-NC{slash}2-Pad15)") (class "Default")
      (node (ref "U2") (pin "15") (pinfunction "NC/2_15") (pintype "unspecified+no_connect"))
    )
    (net (code "43") (name "unconnected-(U2-RX0BF#-Pad12)") (class "Default")
      (node (ref "U2") (pin "12") (pinfunction "RX0BF#_12") (pintype "unspecified+no_connect"))
    )
    (net (code "44") (name "unconnected-(U2-RX1BF#-Pad11)") (class "Default")
      (node (ref "U2") (pin "11") (pinfunction "RX1BF#_11") (pintype "unspecified+no_connect"))
    )
    (net (code "45") (name "unconnected-(U2-TX0RTS#-Pad4)") (class "Default")
      (node (ref "U2") (pin "4") (pinfunction "TX0RTS#_4") (pintype "unspecified+no_connect"))
    )
    (net (code "46") (name "unconnected-(U2-TX1RTS#-Pad5)") (class "Default")
      (node (ref "U2") (pin "5") (pinfunction "TX1RTS#_5") (pintype "unspecified+no_connect"))
    )
    (net (code "47") (name "unconnected-(U2-TX2RTS#-Pad7)") (class "Default")
      (node (ref "U2") (pin "7") (pinfunction "TX2RTS#_7") (pintype "unspecified+no_connect"))
    )
    (net (code "48") (name "unconnected-(U4-NC-Pad5)") (class "Default")
      (node (ref "U4") (pin "5") (pinfunction "NC_5") (pintype "unspecified+no_connect"))
    )
    (net (code "49") (name "unconnected-(U5-MTCK-Pad12)") (class "Default")
      (node (ref "U5") (pin "12") (pinfunction "MTCK_12") (pintype "unspecified+no_connect"))
    )
    (net (code "50") (name "unconnected-(U5-MTDI-Pad10)") (class "Default")
      (node (ref "U5") (pin "10") (pinfunction "MTDI_10") (pintype "unspecified+no_connect"))
    )
    (net (code "51") (name "unconnected-(U5-MTDO-Pad13)") (class "Default")
      (node (ref "U5") (pin "13") (pinfunction "MTDO_13") (pintype "unspecified+no_connect"))
    )
    (net (code "52") (name "unconnected-(U5-SPICLK-Pad22)") (class "Default")
      (node (ref "U5") (pin "22") (pinfunction "SPICLK_22") (pintype "unspecified+no_connect"))
    )
    (net (code "53") (name "unconnected-(U5-SPICS0-Pad21)") (class "Default")
      (node (ref "U5") (pin "21") (pinfunction "SPICS0_21") (pintype "unspecified+no_connect"))
    )
    (net (code "54") (name "unconnected-(U5-SPID-Pad23)") (class "Default")
      (node (ref "U5") (pin "23") (pinfunction "SPID_23") (pintype "unspecified+no_connect"))
    )
    (net (code "55") (name "unconnected-(U5-SPIHD-Pad19)") (class "Default")
      (node (ref "U5") (pin "19") (pinfunction "SPIHD_19") (pintype "unspecified+no_connect"))
    )
    (net (code "56") (name "unconnected-(U5-SPIQ-Pad24)") (class "Default")
      (node (ref "U5") (pin "24") (pinfunction "SPIQ_24") (pintype "unspecified+no_connect"))
    )
    (net (code "57") (name "unconnected-(U5-SPIWP-Pad20)") (class "Default")
      (node (ref "U5") (pin "20") (pinfunction "SPIWP_20") (pintype "unspecified+no_connect"))
    )
    (net (code "58") (name "unconnected-(U5-VDD_SPI-Pad18)") (class "Default")
      (node (ref "U5") (pin "18") (pinfunction "VDD_SPI_18") (pintype "unspecified+no_connect"))
    )
    (net (code "59") (name "unconnected-(USB1-CC1-PadA5)") (class "Default")
      (node (ref "USB1") (pin "A5") (pinfunction "CC1_A5") (pintype "unspecified+no_connect"))
    )
    (net (code "60") (name "unconnected-(USB1-CC2-PadB5)") (class "Default")
      (node (ref "USB1") (pin "B5") (pinfunction "CC2_B5") (pintype "unspecified+no_connect"))
    )
    (net (code "61") (name "unconnected-(USB1-SBU1-PadA8)") (class "Default")
      (node (ref "USB1") (pin "A8") (pinfunction "SBU1_A8") (pintype "unspecified+no_connect"))
    )
    (net (code "62") (name "unconnected-(USB1-SBU2-PadB8)") (class "Default")
      (node (ref "USB1") (pin "B8") (pinfunction "SBU2_B8") (pintype "unspecified+no_connect"))
    )
  )
)
